# logic_probe_v2.net
KiCad netlist of a schematic drawn in EAGLE
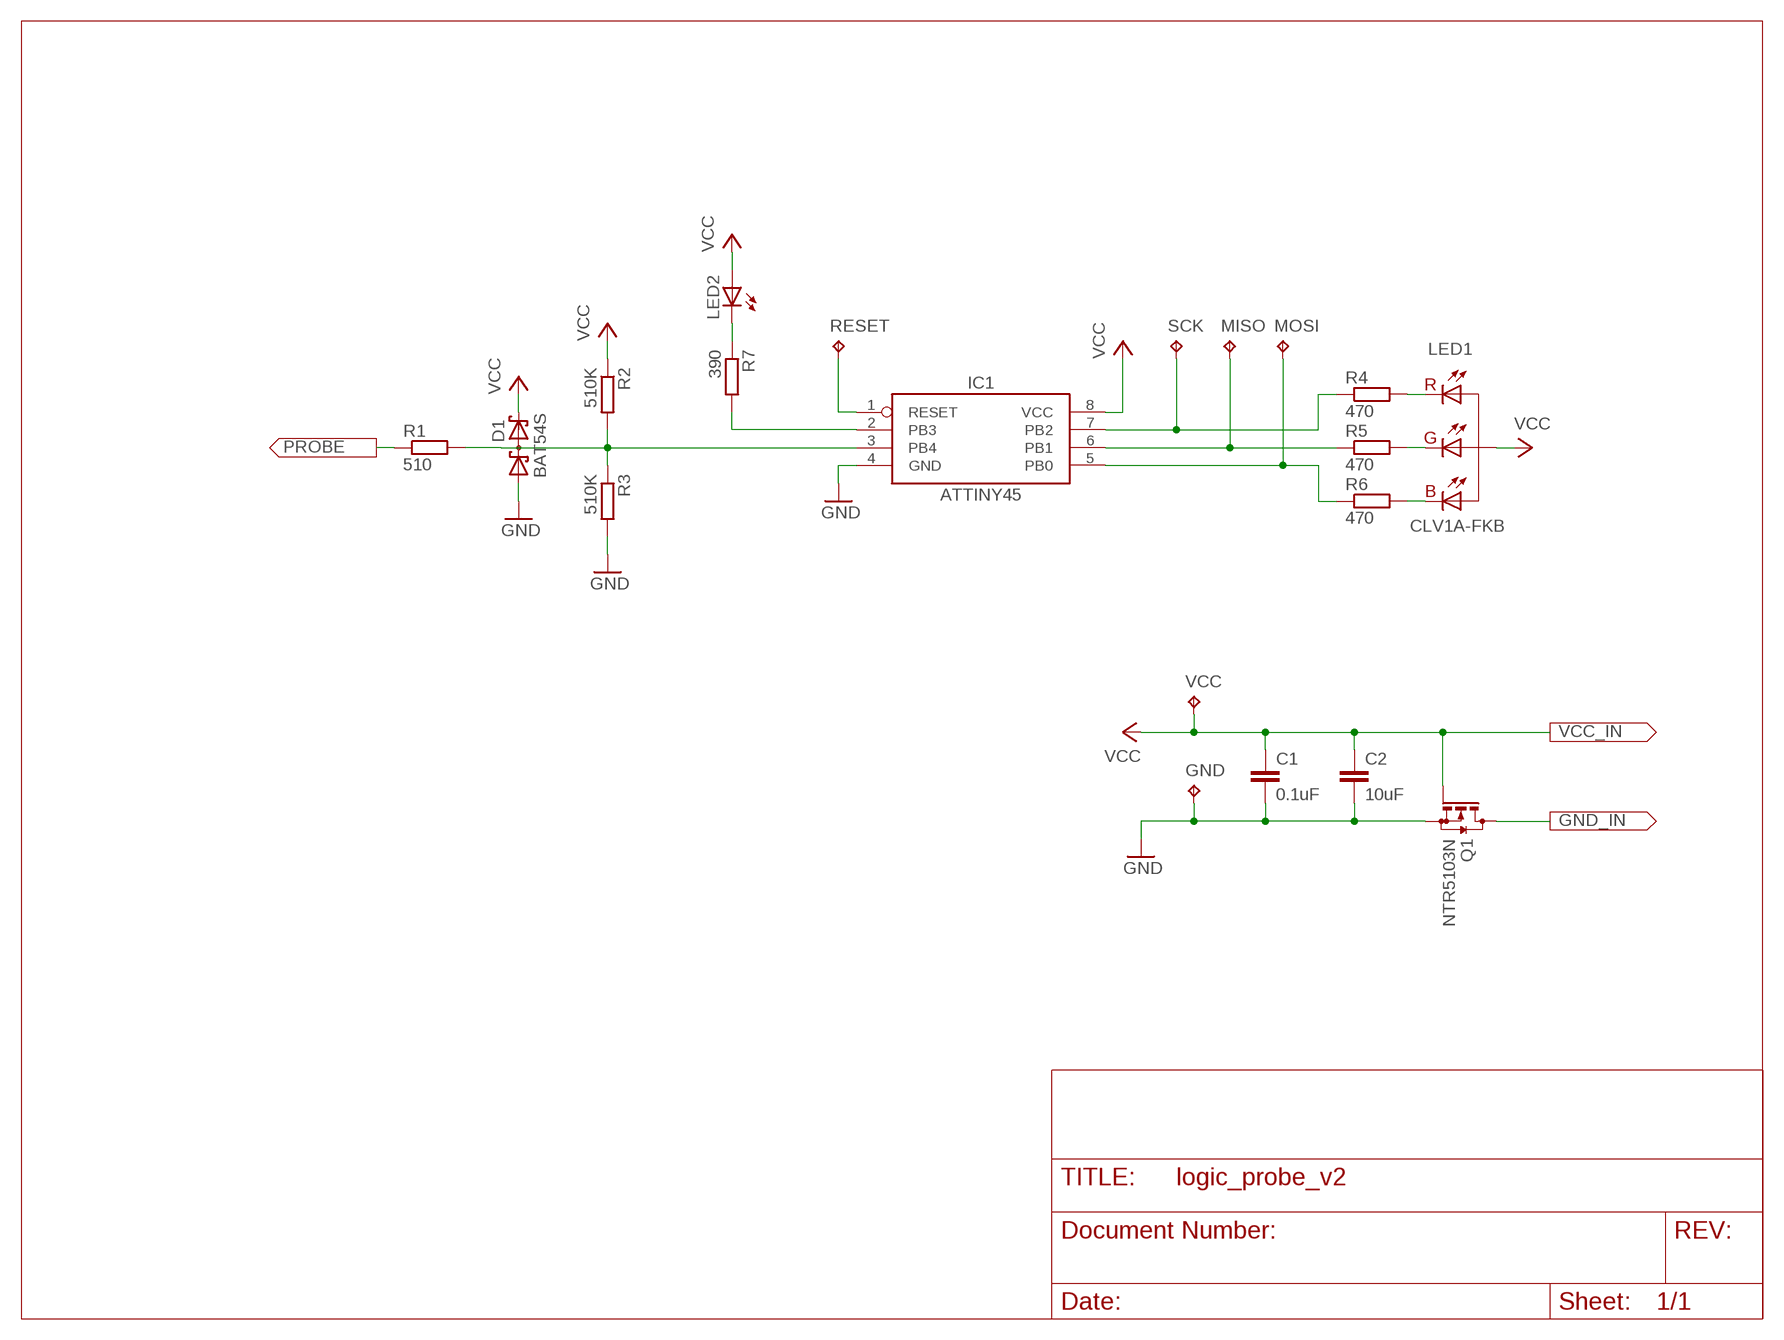
[diagram p0: schematic, sheet 1]

(export (version "E")
  (design (tool "Eeschema 10.0.6"))
  (components
    (comp (ref "C1")
      (value "0.1uF")
      (footprint "eagle-import:C0805")
      (libsource (lib "eagle-import") (part "C-EUC0805"))
    )
    (comp (ref "C2")
      (value "10uF")
      (footprint "eagle-import:C0805")
      (libsource (lib "eagle-import") (part "C-EUC0805"))
    )
    (comp (ref "D1")
      (value "BAT54S")
      (footprint "eagle-import:SOT23")
      (libsource (lib "eagle-import") (part "BAT54S"))
    )
    (comp (ref "GND")
      (value "TPB1,27")
      (footprint "eagle-import:B1,27")
      (libsource (lib "eagle-import") (part "TPB1,27"))
    )
    (comp (ref "IC1")
      (value "ATTINY45")
      (footprint "eagle-import:TSSOP8")
      (libsource (lib "eagle-import") (part "ATTINY45"))
    )
    (comp (ref "LED1")
      (value "CLV1A-FKB")
      (footprint "eagle-import:PLCC-4")
      (libsource (lib "eagle-import") (part "CLV1A-FKB"))
    )
    (comp (ref "LED2")
      (value "LEDCHIPLED_0805")
      (footprint "eagle-import:CHIPLED_0805")
      (libsource (lib "eagle-import") (part "LEDCHIPLED_0805"))
    )
    (comp (ref "MISO")
      (value "TPB1,27")
      (footprint "eagle-import:B1,27")
      (libsource (lib "eagle-import") (part "TPB1,27"))
    )
    (comp (ref "MOSI")
      (value "TPB1,27")
      (footprint "eagle-import:B1,27")
      (libsource (lib "eagle-import") (part "TPB1,27"))
    )
    (comp (ref "Q1")
      (value "NTR5103N")
      (footprint "eagle-import:SOT23")
      (libsource (lib "eagle-import") (part "NTR5103N"))
    )
    (comp (ref "R1")
      (value "510")
      (footprint "eagle-import:R0805")
      (libsource (lib "eagle-import") (part "R-EU_R0805"))
    )
    (comp (ref "R2")
      (value "510K")
      (footprint "eagle-import:R0805")
      (libsource (lib "eagle-import") (part "R-EU_R0805"))
    )
    (comp (ref "R3")
      (value "510K")
      (footprint "eagle-import:R0805")
      (libsource (lib "eagle-import") (part "R-EU_R0805"))
    )
    (comp (ref "R4")
      (value "470")
      (footprint "eagle-import:R0805")
      (libsource (lib "eagle-import") (part "R-EU_R0805"))
    )
    (comp (ref "R5")
      (value "470")
      (footprint "eagle-import:R0805")
      (libsource (lib "eagle-import") (part "R-EU_R0805"))
    )
    (comp (ref "R6")
      (value "470")
      (footprint "eagle-import:R0805")
      (libsource (lib "eagle-import") (part "R-EU_R0805"))
    )
    (comp (ref "R7")
      (value "390")
      (footprint "eagle-import:R0805")
      (libsource (lib "eagle-import") (part "R-EU_R0805"))
    )
    (comp (ref "RESET")
      (value "TPB1,27")
      (footprint "eagle-import:B1,27")
      (libsource (lib "eagle-import") (part "TPB1,27"))
    )
    (comp (ref "SCK")
      (value "TPB1,27")
      (footprint "eagle-import:B1,27")
      (libsource (lib "eagle-import") (part "TPB1,27"))
    )
    (comp (ref "VCC")
      (value "TPB1,27")
      (footprint "eagle-import:B1,27")
      (libsource (lib "eagle-import") (part "TPB1,27"))
    )
  )
  (nets
    (net (code "1") (name "GND") (class "Default")
      (node (ref "C1") (pin "2") (pinfunction "2_2") (pintype "passive"))
      (node (ref "C2") (pin "2") (pinfunction "2_2") (pintype "passive"))
      (node (ref "D1") (pin "1") (pinfunction "A1_1") (pintype "passive"))
      (node (ref "GND") (pin "TP") (pinfunction "TP_TP") (pintype "input"))
      (node (ref "IC1") (pin "4") (pinfunction "GND_4") (pintype "power_in"))
      (node (ref "Q1") (pin "2") (pinfunction "S_2") (pintype "passive"))
      (node (ref "R3") (pin "2") (pinfunction "2_2") (pintype "passive"))
    )
    (net (code "2") (name "Net-(D1-C1A2)") (class "Default")
      (node (ref "D1") (pin "3") (pinfunction "C1A2_3") (pintype "passive"))
      (node (ref "IC1") (pin "3") (pinfunction "PB4_3") (pintype "bidirectional"))
      (node (ref "R1") (pin "2") (pinfunction "2_2") (pintype "passive"))
      (node (ref "R2") (pin "2") (pinfunction "2_2") (pintype "passive"))
      (node (ref "R3") (pin "1") (pinfunction "1_1") (pintype "passive"))
    )
    (net (code "3") (name "Net-(IC1-PB0)") (class "Default")
      (node (ref "IC1") (pin "5") (pinfunction "PB0_5") (pintype "bidirectional"))
      (node (ref "MOSI") (pin "TP") (pinfunction "TP_TP") (pintype "input"))
      (node (ref "R6") (pin "1") (pinfunction "1_1") (pintype "passive"))
    )
    (net (code "4") (name "Net-(IC1-PB1)") (class "Default")
      (node (ref "IC1") (pin "6") (pinfunction "PB1_6") (pintype "bidirectional"))
      (node (ref "MISO") (pin "TP") (pinfunction "TP_TP") (pintype "input"))
      (node (ref "R5") (pin "1") (pinfunction "1_1") (pintype "passive"))
    )
    (net (code "5") (name "Net-(IC1-PB2)") (class "Default")
      (node (ref "IC1") (pin "7") (pinfunction "PB2_7") (pintype "bidirectional"))
      (node (ref "R4") (pin "1") (pinfunction "1_1") (pintype "passive"))
      (node (ref "SCK") (pin "TP") (pinfunction "TP_TP") (pintype "input"))
    )
    (net (code "6") (name "Net-(IC1-PB3)") (class "Default")
      (node (ref "IC1") (pin "2") (pinfunction "PB3_2") (pintype "bidirectional"))
      (node (ref "R7") (pin "2") (pinfunction "2_2") (pintype "passive"))
    )
    (net (code "7") (name "Net-(IC1-RESET)") (class "Default")
      (node (ref "IC1") (pin "1") (pinfunction "RESET_1") (pintype "input"))
      (node (ref "RESET") (pin "TP") (pinfunction "TP_TP") (pintype "input"))
    )
    (net (code "8") (name "Net-(LED1-B)") (class "Default")
      (node (ref "LED1") (pin "4") (pinfunction "B_4") (pintype "passive"))
      (node (ref "R6") (pin "2") (pinfunction "2_2") (pintype "passive"))
    )
    (net (code "9") (name "Net-(LED1-G)") (class "Default")
      (node (ref "LED1") (pin "3") (pinfunction "G_3") (pintype "passive"))
      (node (ref "R5") (pin "2") (pinfunction "2_2") (pintype "passive"))
    )
    (net (code "10") (name "Net-(LED1-R)") (class "Default")
      (node (ref "LED1") (pin "1") (pinfunction "R_1") (pintype "passive"))
      (node (ref "R4") (pin "2") (pinfunction "2_2") (pintype "passive"))
    )
    (net (code "11") (name "Net-(LED2-PadC)") (class "Default")
      (node (ref "LED2") (pin "C") (pinfunction "C_C") (pintype "passive"))
      (node (ref "R7") (pin "1") (pinfunction "1_1") (pintype "passive"))
    )
    (net (code "12") (name "VCC") (class "Default")
      (node (ref "C1") (pin "1") (pinfunction "1_1") (pintype "passive"))
      (node (ref "C2") (pin "1") (pinfunction "1_1") (pintype "passive"))
      (node (ref "D1") (pin "2") (pinfunction "C2_2") (pintype "passive"))
      (node (ref "IC1") (pin "8") (pinfunction "VCC_8") (pintype "power_in"))
      (node (ref "LED1") (pin "2") (pinfunction "CA_2") (pintype "passive"))
      (node (ref "LED2") (pin "A") (pinfunction "A_A") (pintype "passive"))
      (node (ref "Q1") (pin "1") (pinfunction "G_1") (pintype "passive"))
      (node (ref "R2") (pin "1") (pinfunction "1_1") (pintype "passive"))
      (node (ref "VCC") (pin "TP") (pinfunction "TP_TP") (pintype "input"))
    )
    (net (code "13") (name "unconnected-(Q1-D-Pad3)") (class "Default")
      (node (ref "Q1") (pin "3") (pinfunction "D_3") (pintype "passive"))
    )
    (net (code "14") (name "unconnected-(R1-Pad1)") (class "Default")
      (node (ref "R1") (pin "1") (pinfunction "1_1") (pintype "passive"))
    )
  )
)
